# Fri3d_2020_Time_Blaster_01.net
KiCad netlist of a schematic drawn in Altium Designer
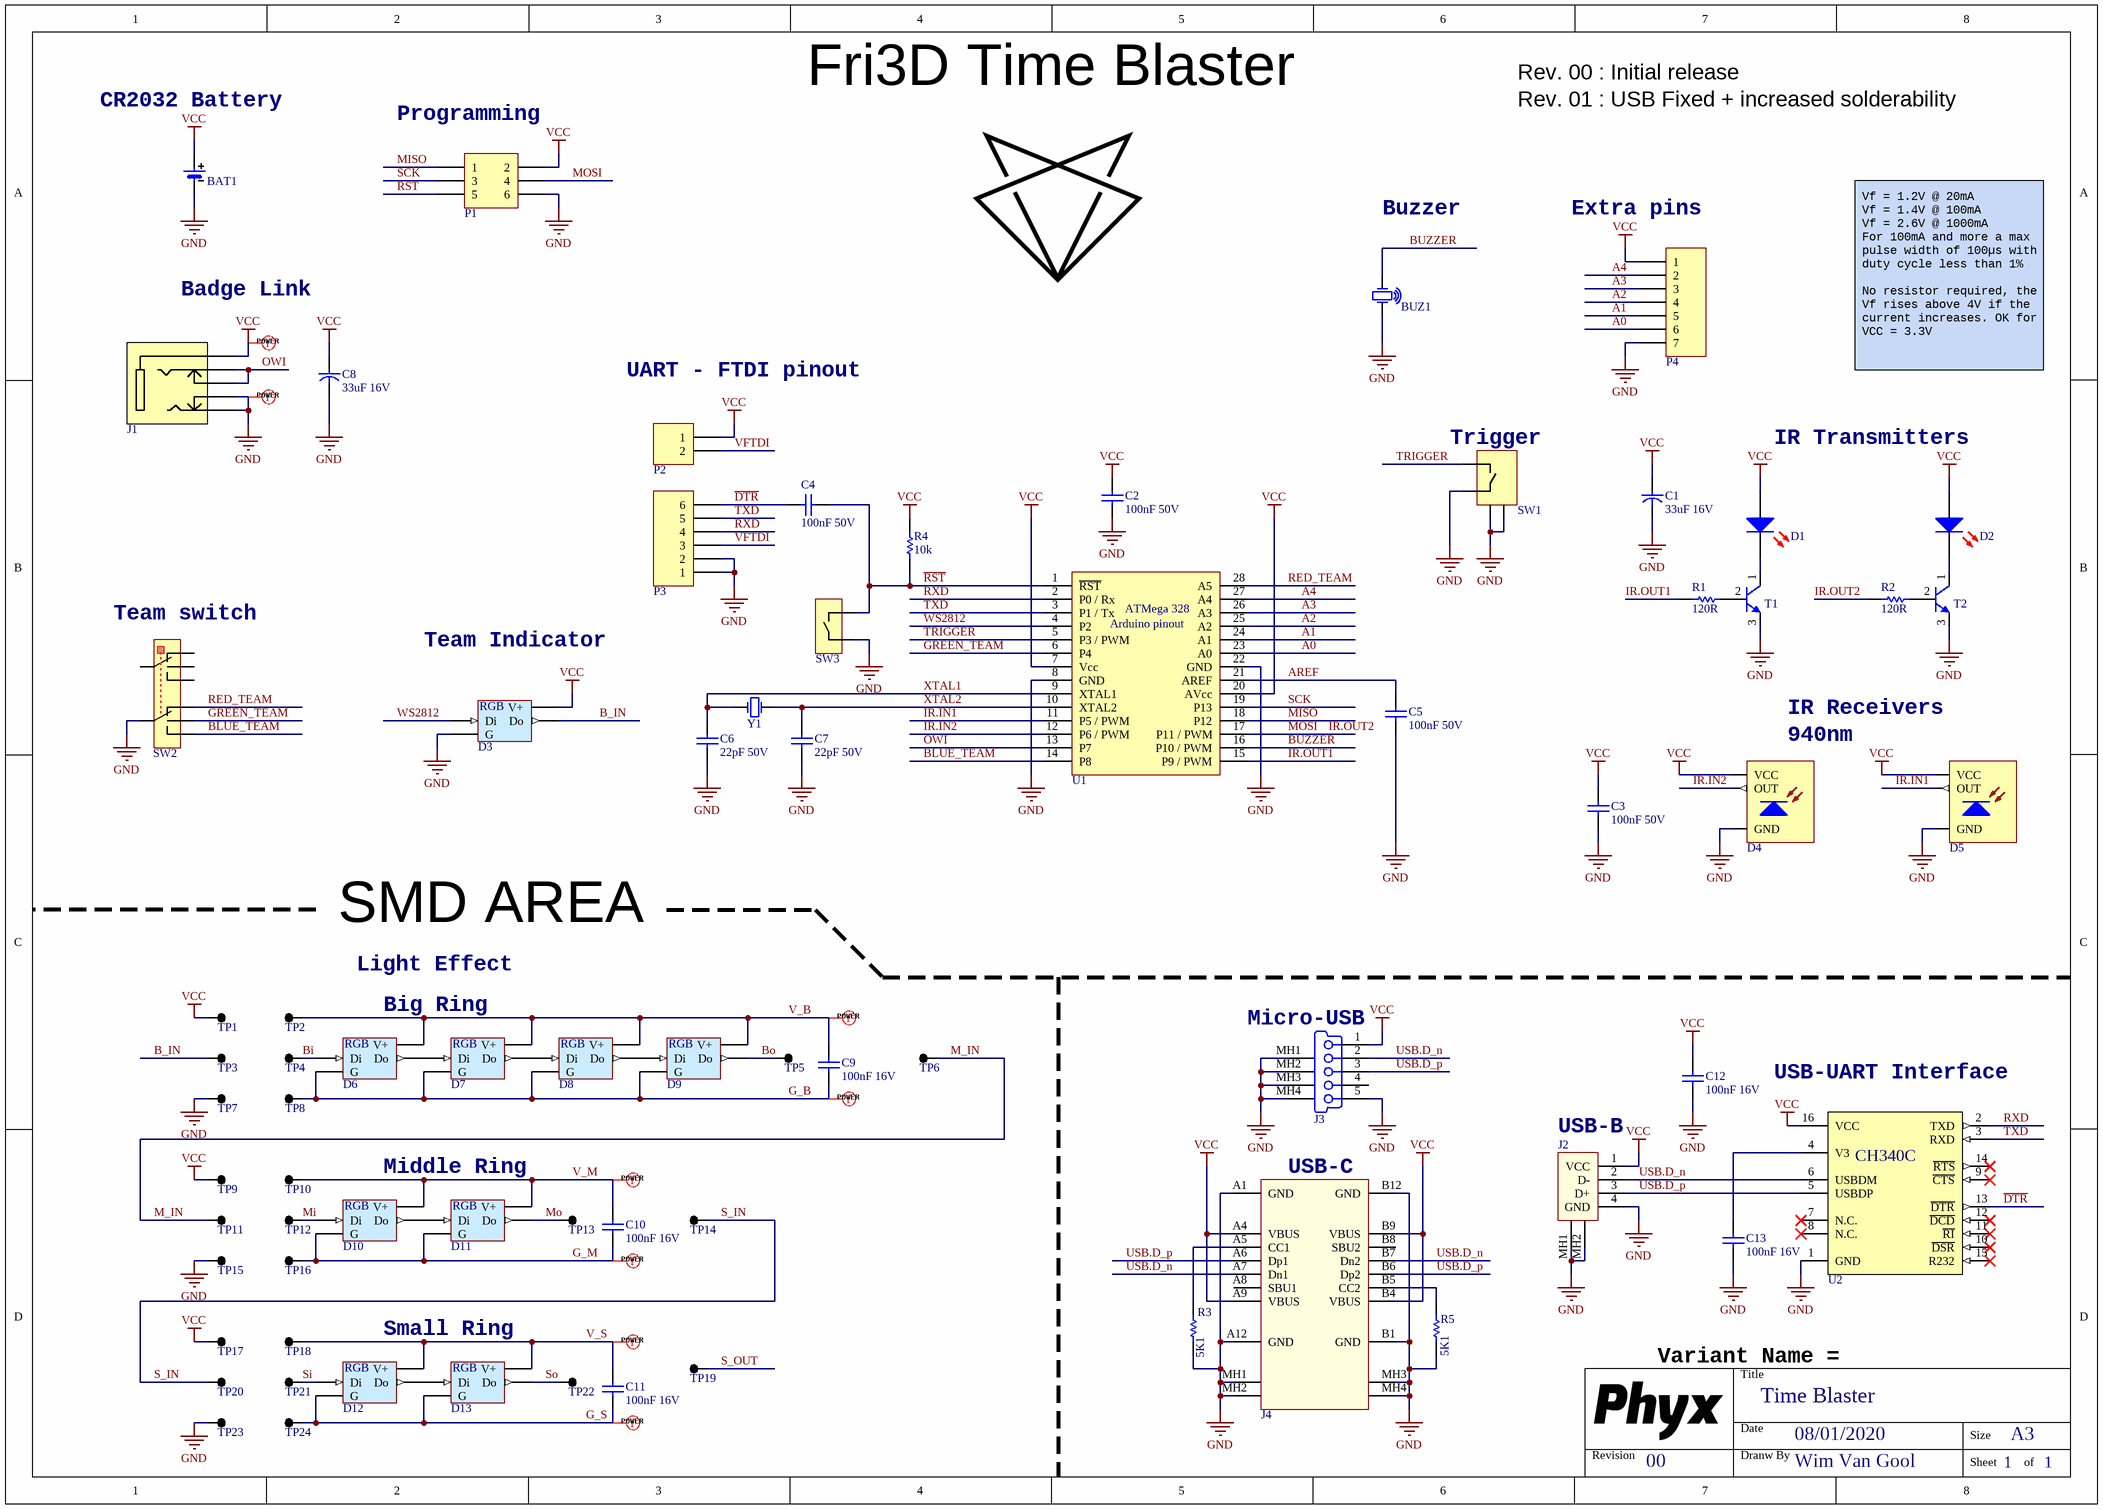
[diagram p0: Fri3d_2020_Time_Blaster_01.SchDoc]

(export (version "E")
  (design (tool "Eeschema 10.0.6"))
  (components
    (comp (ref "BAT1")
      (value "CR2032 Battery Holder")
      (footprint "BAT_CR2032_China")
      (description "=Description")
      (libsource (lib "Phyx_Components") (part "BAT_2"))
    )
    (comp (ref "BUZ1")
      (value "14x14x7mm Piezo Buzzer Transducer 80dB")
      (footprint "CUI_CEP-1162")
      (description "Crystal Oscillator")
      (libsource (lib "Phyx_Components") (part "Buzzer"))
    )
    (comp (ref "C1")
      (value "33uF 16V")
      (footprint "C_4x7_1.5mm")
      (description "Capacitor electrolyt")
      (fields (field (name "Comment") "CAP_POL"))
      (libsource (lib "Phyx_Components") (part "CAP_POL"))
    )
    (comp (ref "C2")
      (value "100nF 50V")
      (footprint "C_5.08mm")
      (description "Capacitor Ceramic")
      (fields (field (name "Comment") "CAP_CERAMIC"))
      (libsource (lib "Phyx_Components") (part "CAP_CERAMIC"))
    )
    (comp (ref "C3")
      (value "100nF 50V")
      (footprint "C_5.08mm")
      (description "Capacitor Ceramic")
      (fields (field (name "Comment") "CAP_CERAMIC"))
      (libsource (lib "Phyx_Components") (part "CAP_CERAMIC"))
    )
    (comp (ref "C4")
      (value "100nF 50V")
      (footprint "C_5.08mm")
      (description "Capacitor Ceramic")
      (fields (field (name "Comment") "CAP_CERAMIC"))
      (libsource (lib "Phyx_Components") (part "CAP_CERAMIC"))
    )
    (comp (ref "C5")
      (value "100nF 50V")
      (footprint "C_5.08mm")
      (description "Capacitor Ceramic")
      (fields (field (name "Comment") "CAP_CERAMIC"))
      (libsource (lib "Phyx_Components") (part "CAP_CERAMIC"))
    )
    (comp (ref "C6")
      (value "22pF 50V")
      (footprint "C_5.08mm")
      (description "Capacitor Ceramic")
      (fields (field (name "Comment") "CAP_CERAMIC"))
      (libsource (lib "Phyx_Components") (part "CAP_CERAMIC"))
    )
    (comp (ref "C7")
      (value "22pF 50V")
      (footprint "C_5.08mm")
      (description "Capacitor Ceramic")
      (fields (field (name "Comment") "CAP_CERAMIC"))
      (libsource (lib "Phyx_Components") (part "CAP_CERAMIC"))
    )
    (comp (ref "C8")
      (value "33uF 16V")
      (footprint "C_4x7_1.5mm")
      (description "Capacitor electrolyt")
      (fields (field (name "Comment") "CAP_POL"))
      (libsource (lib "Phyx_Components") (part "CAP_POL"))
    )
    (comp (ref "C9")
      (value "100nF 16V")
      (footprint "C0805_N")
      (description "Capacitor Ceramic")
      (fields (field (name "Comment") "CAP_CERAMIC"))
      (libsource (lib "Phyx_Components") (part "CAP_CERAMIC"))
    )
    (comp (ref "C10")
      (value "100nF 16V")
      (footprint "C0805_N")
      (description "Capacitor Ceramic")
      (fields (field (name "Comment") "CAP_CERAMIC"))
      (libsource (lib "Phyx_Components") (part "CAP_CERAMIC"))
    )
    (comp (ref "C11")
      (value "100nF 16V")
      (footprint "C0805_N")
      (description "Capacitor Ceramic")
      (fields (field (name "Comment") "CAP_CERAMIC"))
      (libsource (lib "Phyx_Components") (part "CAP_CERAMIC"))
    )
    (comp (ref "C12")
      (value "100nF 16V")
      (footprint "C0805_N")
      (description "Capacitor Ceramic")
      (fields (field (name "Comment") "CAP_CERAMIC"))
      (libsource (lib "Phyx_Components") (part "CAP_CERAMIC"))
    )
    (comp (ref "C13")
      (value "100nF 16V")
      (footprint "C0805_N")
      (description "Capacitor Ceramic")
      (fields (field (name "Comment") "CAP_CERAMIC"))
      (libsource (lib "Phyx_Components") (part "CAP_CERAMIC"))
    )
    (comp (ref "D1")
      (value "5mm IR LED, 940nm, 100mA, 1.35V, 25Deg")
      (footprint "LED_5MM_RD")
      (description "=Description")
      (libsource (lib "Phyx_Components") (part "LED_RED"))
    )
    (comp (ref "D2")
      (value "5mm IR LED, 940nm, 100mA, 1.35V, 25Deg")
      (footprint "LED_5MM_RD")
      (description "=Description")
      (libsource (lib "Phyx_Components") (part "LED_RED"))
    )
    (comp (ref "D3")
      (value "WS2812 based digital RGB LED 5mm")
      (footprint "LED_5mm_RGB")
      (description "=Description")
      (libsource (lib "Phyx_Components") (part "LED_RGB_WS2812B_5mm"))
    )
    (comp (ref "D4")
      (value "IRM-3638N3F14 Infrared Receiver 38 kHz 45° 2.7-5.5V")
      (footprint "VIS_TSOP381x_BENT")
      (description "=Description")
      (libsource (lib "Phyx_Components") (part "PHO_IR_TSOP381x"))
    )
    (comp (ref "D5")
      (value "IRM-3638N3F14 Infrared Receiver 38 kHz 45° 2.7-5.5V")
      (footprint "VIS_TSOP381x_BENT")
      (description "=Description")
      (libsource (lib "Phyx_Components") (part "PHO_IR_TSOP381x"))
    )
    (comp (ref "D6")
      (value "WS2812 based digital RGB LED 5050 Black package")
      (footprint "LED_5050_WS2812B_BLACK")
      (description "=Description")
      (libsource (lib "Phyx_Components") (part "LED_RGB_WS2812B_5050"))
    )
    (comp (ref "D7")
      (value "WS2812 based digital RGB LED 5050 Black package")
      (footprint "LED_5050_WS2812B_BLACK")
      (description "=Description")
      (libsource (lib "Phyx_Components") (part "LED_RGB_WS2812B_5050"))
    )
    (comp (ref "D8")
      (value "WS2812 based digital RGB LED 5050 Black package")
      (footprint "LED_5050_WS2812B_BLACK")
      (description "=Description")
      (libsource (lib "Phyx_Components") (part "LED_RGB_WS2812B_5050"))
    )
    (comp (ref "D9")
      (value "WS2812 based digital RGB LED 5050 Black package")
      (footprint "LED_5050_WS2812B_BLACK")
      (description "=Description")
      (libsource (lib "Phyx_Components") (part "LED_RGB_WS2812B_5050"))
    )
    (comp (ref "D10")
      (value "WS2812 based digital RGB LED 5050 Black package")
      (footprint "LED_5050_WS2812B_BLACK")
      (description "=Description")
      (libsource (lib "Phyx_Components") (part "LED_RGB_WS2812B_5050"))
    )
    (comp (ref "D11")
      (value "WS2812 based digital RGB LED 5050 Black package")
      (footprint "LED_5050_WS2812B_BLACK")
      (description "=Description")
      (libsource (lib "Phyx_Components") (part "LED_RGB_WS2812B_5050"))
    )
    (comp (ref "D12")
      (value "WS2812 based digital RGB LED 5050 Black package")
      (footprint "LED_5050_WS2812B_BLACK")
      (description "=Description")
      (libsource (lib "Phyx_Components") (part "LED_RGB_WS2812B_5050"))
    )
    (comp (ref "D13")
      (value "WS2812 based digital RGB LED 5050 Black package")
      (footprint "LED_5050_WS2812B_BLACK")
      (description "=Description")
      (libsource (lib "Phyx_Components") (part "LED_RGB_WS2812B_5050"))
    )
    (comp (ref "J1")
      (value "3.5mm jack, dual switch, black, 3 contacts")
      (footprint "CUI_SJ1-3525NG")
      (description "=Description")
      (libsource (lib "Phyx_Components") (part "CUI_SJ1-3525NG"))
    )
    (comp (ref "J2")
      (value "Vertical USB B 61400416121")
      (footprint "WE_61400416121")
      (libsource (lib "Phyx_Components") (part "USB_A"))
    )
    (comp (ref "J3")
      (value "XKB U254-051T-4BH81-S2S Micro USB")
      (footprint "XKB_U254-051T-4BH81-S2S")
      (libsource (lib "Phyx_Components") (part "USB_OTG_Mini-B"))
    )
    (comp (ref "J4")
      (value "USB 2.0 C Reversible Receptacle Horizontal")
      (footprint "HRO_TYPE-C-31-M-12")
      (libsource (lib "Phyx_Components") (part "USB_C_16_4"))
    )
    (comp (ref "P1")
      (value "Boxed Header 3X2")
      (footprint "B_HDR2X3")
      (libsource (lib "Phyx_Components") (part "Header 3X2"))
    )
    (comp (ref "P2")
      (value "Easy to solder connection")
      (footprint "SOLDER_SW_V_1MM")
      (libsource (lib "Phyx_Components") (part "Header 2"))
    )
    (comp (ref "P3")
      (value "Header 6")
      (footprint "HDR1X6")
      (libsource (lib "Phyx_Components") (part "Header 6"))
    )
    (comp (ref "P4")
      (value "Header 7")
      (footprint "HDR1X7")
      (libsource (lib "Phyx_Components") (part "Header 7"))
    )
    (comp (ref "R1")
      (value "120R")
      (footprint "RES_10mm")
      (fields (field (name "Comment") "RESISTOR"))
      (libsource (lib "Phyx_Components") (part "RESISTOR"))
    )
    (comp (ref "R2")
      (value "120R")
      (footprint "RES_10mm")
      (fields (field (name "Comment") "RESISTOR"))
      (libsource (lib "Phyx_Components") (part "RESISTOR"))
    )
    (comp (ref "R3")
      (value "5K1")
      (footprint "R0805_N")
      (fields (field (name "Comment") "RESISTOR"))
      (libsource (lib "Phyx_Components") (part "RESISTOR"))
    )
    (comp (ref "R4")
      (value "10k")
      (footprint "RES_10mm")
      (fields (field (name "Comment") "RESISTOR"))
      (libsource (lib "Phyx_Components") (part "RESISTOR"))
    )
    (comp (ref "R5")
      (value "5K1")
      (footprint "R0805_N")
      (fields (field (name "Comment") "RESISTOR"))
      (libsource (lib "Phyx_Components") (part "RESISTOR"))
    )
    (comp (ref "SW1")
      (value "Tact switch, RA, 3,85mm")
      (footprint "TACTSW_RA_385")
      (libsource (lib "Phyx_Components") (part "SW_TACT_RA"))
    )
    (comp (ref "SW2")
      (value "Slide switch dual pole triple throw")
      (footprint "CK_JS203011CQN")
      (libsource (lib "Phyx_Components") (part "SW_2P3T"))
    )
    (comp (ref "SW3")
      (value "Default TH TACT")
      (footprint "TACTSW")
      (libsource (lib "Phyx_Components") (part "SW_TACT"))
    )
    (comp (ref "T1")
      (value "0.2A 40V 100hfe NPN Transistor")
      (footprint "TO-92A _EASY")
      (libsource (lib "Phyx_Components") (part "NPN_EBC"))
    )
    (comp (ref "T2")
      (value "0.2A 40V 100hfe NPN Transistor")
      (footprint "TO-92A _EASY")
      (libsource (lib "Phyx_Components") (part "NPN_EBC"))
    )
    (comp (ref "TP1")
      (value "TEST_PAD")
      (footprint "TP_2x3mm")
      (libsource (lib "Phyx_Components") (part "TEST_PAD"))
    )
    (comp (ref "TP2")
      (value "TEST_PAD")
      (footprint "TP_2x3mm")
      (libsource (lib "Phyx_Components") (part "TEST_PAD"))
    )
    (comp (ref "TP3")
      (value "TEST_PAD")
      (footprint "TP_2x3mm")
      (libsource (lib "Phyx_Components") (part "TEST_PAD"))
    )
    (comp (ref "TP4")
      (value "TEST_PAD")
      (footprint "TP_2x3mm")
      (libsource (lib "Phyx_Components") (part "TEST_PAD"))
    )
    (comp (ref "TP5")
      (value "TEST_PAD")
      (footprint "TP_2x3mm")
      (libsource (lib "Phyx_Components") (part "TEST_PAD"))
    )
    (comp (ref "TP6")
      (value "TEST_PAD")
      (footprint "TP_2x3mm")
      (libsource (lib "Phyx_Components") (part "TEST_PAD"))
    )
    (comp (ref "TP7")
      (value "TEST_PAD")
      (footprint "TP_2x3mm")
      (libsource (lib "Phyx_Components") (part "TEST_PAD"))
    )
    (comp (ref "TP8")
      (value "TEST_PAD")
      (footprint "TP_2x3mm")
      (libsource (lib "Phyx_Components") (part "TEST_PAD"))
    )
    (comp (ref "TP9")
      (value "TEST_PAD")
      (footprint "TP_2x3mm")
      (libsource (lib "Phyx_Components") (part "TEST_PAD"))
    )
    (comp (ref "TP10")
      (value "TEST_PAD")
      (footprint "TP_2x3mm")
      (libsource (lib "Phyx_Components") (part "TEST_PAD"))
    )
    (comp (ref "TP11")
      (value "TEST_PAD")
      (footprint "TP_2x3mm")
      (libsource (lib "Phyx_Components") (part "TEST_PAD"))
    )
    (comp (ref "TP12")
      (value "TEST_PAD")
      (footprint "TP_2x3mm")
      (libsource (lib "Phyx_Components") (part "TEST_PAD"))
    )
    (comp (ref "TP13")
      (value "TEST_PAD")
      (footprint "TP_2x3mm")
      (libsource (lib "Phyx_Components") (part "TEST_PAD"))
    )
    (comp (ref "TP14")
      (value "TEST_PAD")
      (footprint "TP_2x3mm")
      (libsource (lib "Phyx_Components") (part "TEST_PAD"))
    )
    (comp (ref "TP15")
      (value "TEST_PAD")
      (footprint "TP_2x3mm")
      (libsource (lib "Phyx_Components") (part "TEST_PAD"))
    )
    (comp (ref "TP16")
      (value "TEST_PAD")
      (footprint "TP_2x3mm")
      (libsource (lib "Phyx_Components") (part "TEST_PAD"))
    )
    (comp (ref "TP17")
      (value "TEST_PAD")
      (footprint "TP_2x3mm")
      (libsource (lib "Phyx_Components") (part "TEST_PAD"))
    )
    (comp (ref "TP18")
      (value "TEST_PAD")
      (footprint "TP_2x3mm")
      (libsource (lib "Phyx_Components") (part "TEST_PAD"))
    )
    (comp (ref "TP19")
      (value "TEST_PAD")
      (footprint "TP_2x3mm")
      (libsource (lib "Phyx_Components") (part "TEST_PAD"))
    )
    (comp (ref "TP20")
      (value "TEST_PAD")
      (footprint "TP_2x3mm")
      (libsource (lib "Phyx_Components") (part "TEST_PAD"))
    )
    (comp (ref "TP21")
      (value "TEST_PAD")
      (footprint "TP_2x3mm")
      (libsource (lib "Phyx_Components") (part "TEST_PAD"))
    )
    (comp (ref "TP22")
      (value "TEST_PAD")
      (footprint "TP_2x3mm")
      (libsource (lib "Phyx_Components") (part "TEST_PAD"))
    )
    (comp (ref "TP23")
      (value "TEST_PAD")
      (footprint "TP_2x3mm")
      (libsource (lib "Phyx_Components") (part "TEST_PAD"))
    )
    (comp (ref "TP24")
      (value "TEST_PAD")
      (footprint "TP_2x3mm")
      (libsource (lib "Phyx_Components") (part "TEST_PAD"))
    )
    (comp (ref "U1")
      (value "8-bit MCU")
      (footprint "DIP_N_28")
      (libsource (lib "Phyx_Components") (part "ATMega328_DIP28"))
    )
    (comp (ref "U2")
      (value "USB to full UART with internal crystal")
      (footprint "SOIC_N_16")
      (description "=Description")
      (libsource (lib "Phyx_Components") (part "CH340C"))
    )
    (comp (ref "Y1")
      (value "16MHz 18pF HC49US")
      (footprint "HC49US")
      (description "Crystal Oscillator")
      (libsource (lib "Phyx_Components") (part "XTAL"))
    )
  )
  (nets
    (net (code "1") (name "/A0") (class "Default")
      (node (ref "P4") (pin "6") (pinfunction "6_6") (pintype "passive"))
      (node (ref "U1") (pin "23") (pinfunction "A0_23") (pintype "passive"))
    )
    (net (code "2") (name "/A1") (class "Default")
      (node (ref "P4") (pin "5") (pinfunction "5_5") (pintype "passive"))
      (node (ref "U1") (pin "24") (pinfunction "A1_24") (pintype "passive"))
    )
    (net (code "3") (name "/A2") (class "Default")
      (node (ref "P4") (pin "4") (pinfunction "4_4") (pintype "passive"))
      (node (ref "U1") (pin "25") (pinfunction "A2_25") (pintype "passive"))
    )
    (net (code "4") (name "/A3") (class "Default")
      (node (ref "P4") (pin "3") (pinfunction "3_3") (pintype "passive"))
      (node (ref "U1") (pin "26") (pinfunction "A3_26") (pintype "passive"))
    )
    (net (code "5") (name "/A4") (class "Default")
      (node (ref "P4") (pin "2") (pinfunction "2_2") (pintype "passive"))
      (node (ref "U1") (pin "27") (pinfunction "A4_27") (pintype "passive"))
    )
    (net (code "6") (name "/AREF") (class "Default")
      (node (ref "C5") (pin "1") (pinfunction "1_1") (pintype "passive"))
      (node (ref "U1") (pin "21") (pinfunction "AREF_21") (pintype "passive"))
    )
    (net (code "7") (name "/BLUE_TEAM") (class "Default")
      (node (ref "SW2") (pin "8") (pinfunction "8_8") (pintype "passive"))
      (node (ref "U1") (pin "14") (pinfunction "P8_14") (pintype "passive"))
    )
    (net (code "8") (name "/BUZZER") (class "Default")
      (node (ref "BUZ1") (pin "2") (pinfunction "OSC2_2") (pintype "passive"))
      (node (ref "U1") (pin "16") (pinfunction "P10_/_PWM_16") (pintype "passive"))
    )
    (net (code "9") (name "/B_IN") (class "Default")
      (node (ref "D3") (pin "1") (pinfunction "Do_1") (pintype "output"))
      (node (ref "TP3") (pin "1") (pinfunction "1_1") (pintype "passive"))
    )
    (net (code "10") (name "/Bi") (class "Default")
      (node (ref "D6") (pin "4") (pinfunction "Di_4") (pintype "input"))
      (node (ref "TP4") (pin "1") (pinfunction "1_1") (pintype "passive"))
    )
    (net (code "11") (name "/Bo") (class "Default")
      (node (ref "D9") (pin "2") (pinfunction "Do_2") (pintype "output"))
      (node (ref "TP5") (pin "1") (pinfunction "1_1") (pintype "passive"))
    )
    (net (code "12") (name "/GREEN_TEAM") (class "Default")
      (node (ref "SW2") (pin "6") (pinfunction "6_6") (pintype "passive"))
      (node (ref "U1") (pin "6") (pinfunction "P4_6") (pintype "passive"))
    )
    (net (code "13") (name "/G_B") (class "Default")
      (node (ref "C9") (pin "2") (pinfunction "2_2") (pintype "passive"))
      (node (ref "D6") (pin "3") (pinfunction "G_3") (pintype "power_in"))
      (node (ref "D7") (pin "3") (pinfunction "G_3") (pintype "power_in"))
      (node (ref "D8") (pin "3") (pinfunction "G_3") (pintype "power_in"))
      (node (ref "D9") (pin "3") (pinfunction "G_3") (pintype "power_in"))
      (node (ref "TP8") (pin "1") (pinfunction "1_1") (pintype "passive"))
    )
    (net (code "14") (name "/G_M") (class "Default")
      (node (ref "C10") (pin "2") (pinfunction "2_2") (pintype "passive"))
      (node (ref "D10") (pin "3") (pinfunction "G_3") (pintype "power_in"))
      (node (ref "D11") (pin "3") (pinfunction "G_3") (pintype "power_in"))
      (node (ref "TP16") (pin "1") (pinfunction "1_1") (pintype "passive"))
    )
    (net (code "15") (name "/G_S") (class "Default")
      (node (ref "C11") (pin "2") (pinfunction "2_2") (pintype "passive"))
      (node (ref "D12") (pin "3") (pinfunction "G_3") (pintype "power_in"))
      (node (ref "D13") (pin "3") (pinfunction "G_3") (pintype "power_in"))
      (node (ref "TP24") (pin "1") (pinfunction "1_1") (pintype "passive"))
    )
    (net (code "16") (name "/IR.IN1") (class "Default")
      (node (ref "D5") (pin "1") (pinfunction "OUT_1") (pintype "output"))
      (node (ref "U1") (pin "11") (pinfunction "P5_/_PWM_11") (pintype "passive"))
    )
    (net (code "17") (name "/IR.IN2") (class "Default")
      (node (ref "D4") (pin "1") (pinfunction "OUT_1") (pintype "output"))
      (node (ref "U1") (pin "12") (pinfunction "P6_/_PWM_12") (pintype "passive"))
    )
    (net (code "18") (name "/IR.OUT1") (class "Default")
      (node (ref "R1") (pin "2") (pinfunction "2_2") (pintype "passive"))
      (node (ref "U1") (pin "15") (pinfunction "P9_/_PWM_15") (pintype "passive"))
    )
    (net (code "19") (name "/IR.OUT2") (class "Default")
      (node (ref "P1") (pin "4") (pinfunction "4_4") (pintype "passive"))
      (node (ref "R2") (pin "2") (pinfunction "2_2") (pintype "passive"))
      (node (ref "U1") (pin "17") (pinfunction "P11_/_PWM_17") (pintype "passive"))
    )
    (net (code "20") (name "/MISO") (class "Default")
      (node (ref "P1") (pin "1") (pinfunction "1_1") (pintype "passive"))
      (node (ref "U1") (pin "18") (pinfunction "P12_18") (pintype "passive"))
    )
    (net (code "21") (name "/M_IN") (class "Default")
      (node (ref "TP11") (pin "1") (pinfunction "1_1") (pintype "passive"))
      (node (ref "TP6") (pin "1") (pinfunction "1_1") (pintype "passive"))
    )
    (net (code "22") (name "/Mi") (class "Default")
      (node (ref "D10") (pin "4") (pinfunction "Di_4") (pintype "input"))
      (node (ref "TP12") (pin "1") (pinfunction "1_1") (pintype "passive"))
    )
    (net (code "23") (name "/Mo") (class "Default")
      (node (ref "D11") (pin "2") (pinfunction "Do_2") (pintype "output"))
      (node (ref "TP13") (pin "1") (pinfunction "1_1") (pintype "passive"))
    )
    (net (code "24") (name "/OWI") (class "Default")
      (node (ref "J1") (pin "3") (pinfunction "Ring_3") (pintype "passive"))
      (node (ref "J1") (pin "5") (pinfunction "5_5") (pintype "passive"))
      (node (ref "U1") (pin "13") (pinfunction "P7_13") (pintype "passive"))
    )
    (net (code "25") (name "/RED_TEAM") (class "Default")
      (node (ref "SW2") (pin "5") (pinfunction "5_5") (pintype "passive"))
      (node (ref "U1") (pin "28") (pinfunction "A5_28") (pintype "passive"))
    )
    (net (code "26") (name "/RXD") (class "Default")
      (node (ref "P3") (pin "4") (pinfunction "4_4") (pintype "passive"))
      (node (ref "U1") (pin "2") (pinfunction "P0_/_Rx_2") (pintype "passive"))
      (node (ref "U2") (pin "2") (pinfunction "TXD_2") (pintype "output"))
    )
    (net (code "27") (name "/SCK") (class "Default")
      (node (ref "P1") (pin "3") (pinfunction "3_3") (pintype "passive"))
      (node (ref "U1") (pin "19") (pinfunction "P13_19") (pintype "passive"))
    )
    (net (code "28") (name "/S_IN") (class "Default")
      (node (ref "TP14") (pin "1") (pinfunction "1_1") (pintype "passive"))
      (node (ref "TP20") (pin "1") (pinfunction "1_1") (pintype "passive"))
    )
    (net (code "29") (name "/S_OUT") (class "Default")
      (node (ref "TP19") (pin "1") (pinfunction "1_1") (pintype "passive"))
    )
    (net (code "30") (name "/Si") (class "Default")
      (node (ref "D12") (pin "4") (pinfunction "Di_4") (pintype "input"))
      (node (ref "TP21") (pin "1") (pinfunction "1_1") (pintype "passive"))
    )
    (net (code "31") (name "/So") (class "Default")
      (node (ref "D13") (pin "2") (pinfunction "Do_2") (pintype "output"))
      (node (ref "TP22") (pin "1") (pinfunction "1_1") (pintype "passive"))
    )
    (net (code "32") (name "/TRIGGER") (class "Default")
      (node (ref "SW1") (pin "1") (pinfunction "1_1") (pintype "passive"))
      (node (ref "U1") (pin "5") (pinfunction "P3_/_PWM_5") (pintype "passive"))
    )
    (net (code "33") (name "/TXD") (class "Default")
      (node (ref "P3") (pin "5") (pinfunction "5_5") (pintype "passive"))
      (node (ref "U1") (pin "3") (pinfunction "P1_/_Tx_3") (pintype "passive"))
      (node (ref "U2") (pin "3") (pinfunction "RXD_3") (pintype "input"))
    )
    (net (code "34") (name "/USB.D_n") (class "Default")
      (node (ref "J2") (pin "2") (pinfunction "D-_2") (pintype "passive"))
      (node (ref "J3") (pin "2") (pinfunction "D-_2") (pintype "passive"))
      (node (ref "J4") (pin "A7") (pinfunction "Dn1_A7") (pintype "passive"))
      (node (ref "J4") (pin "B7") (pinfunction "Dn2_B7") (pintype "passive"))
      (node (ref "U2") (pin "6") (pinfunction "USBDM_6") (pintype "passive"))
    )
    (net (code "35") (name "/USB.D_p") (class "Default")
      (node (ref "J2") (pin "3") (pinfunction "D+_3") (pintype "passive"))
      (node (ref "J3") (pin "3") (pinfunction "D+_3") (pintype "passive"))
      (node (ref "J4") (pin "A6") (pinfunction "Dp1_A6") (pintype "passive"))
      (node (ref "J4") (pin "B6") (pinfunction "Dp2_B6") (pintype "passive"))
      (node (ref "U2") (pin "5") (pinfunction "USBDP_5") (pintype "passive"))
    )
    (net (code "36") (name "/VFTDI") (class "Default")
      (node (ref "P2") (pin "2") (pinfunction "2_2") (pintype "passive"))
      (node (ref "P3") (pin "3") (pinfunction "3_3") (pintype "passive"))
    )
    (net (code "37") (name "/V_B") (class "Default")
      (node (ref "C9") (pin "1") (pinfunction "1_1") (pintype "passive"))
      (node (ref "D6") (pin "1") (pinfunction "V+_1") (pintype "power_in"))
      (node (ref "D7") (pin "1") (pinfunction "V+_1") (pintype "power_in"))
      (node (ref "D8") (pin "1") (pinfunction "V+_1") (pintype "power_in"))
      (node (ref "D9") (pin "1") (pinfunction "V+_1") (pintype "power_in"))
      (node (ref "TP2") (pin "1") (pinfunction "1_1") (pintype "passive"))
    )
    (net (code "38") (name "/V_M") (class "Default")
      (node (ref "C10") (pin "1") (pinfunction "1_1") (pintype "passive"))
      (node (ref "D10") (pin "1") (pinfunction "V+_1") (pintype "power_in"))
      (node (ref "D11") (pin "1") (pinfunction "V+_1") (pintype "power_in"))
      (node (ref "TP10") (pin "1") (pinfunction "1_1") (pintype "passive"))
    )
    (net (code "39") (name "/V_S") (class "Default")
      (node (ref "C11") (pin "1") (pinfunction "1_1") (pintype "passive"))
      (node (ref "D12") (pin "1") (pinfunction "V+_1") (pintype "power_in"))
      (node (ref "D13") (pin "1") (pinfunction "V+_1") (pintype "power_in"))
      (node (ref "TP18") (pin "1") (pinfunction "1_1") (pintype "passive"))
    )
    (net (code "40") (name "/WS2812") (class "Default")
      (node (ref "D3") (pin "4") (pinfunction "Di_4") (pintype "input"))
      (node (ref "U1") (pin "4") (pinfunction "P2_4") (pintype "passive"))
    )
    (net (code "41") (name "/XTAL1") (class "Default")
      (node (ref "C6") (pin "1") (pinfunction "1_1") (pintype "passive"))
      (node (ref "U1") (pin "9") (pinfunction "XTAL1_9") (pintype "passive"))
      (node (ref "Y1") (pin "1") (pinfunction "OSC1_1") (pintype "passive"))
    )
    (net (code "42") (name "/XTAL2") (class "Default")
      (node (ref "C7") (pin "1") (pinfunction "1_1") (pintype "passive"))
      (node (ref "U1") (pin "10") (pinfunction "XTAL2_10") (pintype "passive"))
      (node (ref "Y1") (pin "2") (pinfunction "OSC2_2") (pintype "passive"))
    )
    (net (code "43") (name "/~{DTR}") (class "Default")
      (node (ref "C4") (pin "2") (pinfunction "2_2") (pintype "passive"))
      (node (ref "P3") (pin "6") (pinfunction "6_6") (pintype "passive"))
      (node (ref "U2") (pin "13") (pinfunction "~{DTR}_13") (pintype "output"))
    )
    (net (code "44") (name "/~{RST}") (class "Default")
      (node (ref "C4") (pin "1") (pinfunction "1_1") (pintype "passive"))
      (node (ref "P1") (pin "5") (pinfunction "5_5") (pintype "passive"))
      (node (ref "R4") (pin "2") (pinfunction "2_2") (pintype "passive"))
      (node (ref "SW3") (pin "1") (pinfunction "1_1") (pintype "passive"))
      (node (ref "U1") (pin "1") (pinfunction "~{RST}_1") (pintype "passive"))
    )
    (net (code "45") (name "GND") (class "Default")
      (node (ref "BAT1") (pin "2") (pinfunction "2_2") (pintype "passive"))
      (node (ref "BUZ1") (pin "1") (pinfunction "OSC1_1") (pintype "passive"))
      (node (ref "C1") (pin "2") (pinfunction "2_2") (pintype "passive"))
      (node (ref "C12") (pin "2") (pinfunction "2_2") (pintype "passive"))
      (node (ref "C13") (pin "2") (pinfunction "2_2") (pintype "passive"))
      (node (ref "C2") (pin "2") (pinfunction "2_2") (pintype "passive"))
      (node (ref "C3") (pin "2") (pinfunction "2_2") (pintype "passive"))
      (node (ref "C5") (pin "2") (pinfunction "2_2") (pintype "passive"))
      (node (ref "C6") (pin "2") (pinfunction "2_2") (pintype "passive"))
      (node (ref "C7") (pin "2") (pinfunction "2_2") (pintype "passive"))
      (node (ref "C8") (pin "2") (pinfunction "2_2") (pintype "passive"))
      (node (ref "D3") (pin "3") (pinfunction "G_3") (pintype "power_in"))
      (node (ref "D4") (pin "2") (pinfunction "GND_2") (pintype "power_in"))
      (node (ref "D5") (pin "2") (pinfunction "GND_2") (pintype "power_in"))
      (node (ref "J1") (pin "2") (pinfunction "Tip_2") (pintype "passive"))
      (node (ref "J1") (pin "4") (pinfunction "4_4") (pintype "passive"))
      (node (ref "J2") (pin "4") (pinfunction "GND_4") (pintype "passive"))
      (node (ref "J2") (pin "MH1") (pinfunction "Tab_MH1") (pintype "passive"))
      (node (ref "J2") (pin "MH2") (pinfunction "Tab_MH2") (pintype "passive"))
      (node (ref "J3") (pin "5") (pinfunction "GND_5") (pintype "passive"))
      (node (ref "J3") (pin "MH1") (pinfunction "Tab_MH1") (pintype "passive"))
      (node (ref "J3") (pin "MH2") (pinfunction "Tab_MH2") (pintype "passive"))
      (node (ref "J3") (pin "MH3") (pinfunction "Tab_MH3") (pintype "passive"))
      (node (ref "J3") (pin "MH4") (pinfunction "Tab_MH4") (pintype "passive"))
      (node (ref "J4") (pin "A1") (pinfunction "GND_A1") (pintype "passive"))
      (node (ref "J4") (pin "A12") (pinfunction "GND_A12") (pintype "passive"))
      (node (ref "J4") (pin "B1") (pinfunction "GND_B1") (pintype "passive"))
      (node (ref "J4") (pin "B12") (pinfunction "GND_B12") (pintype "passive"))
      (node (ref "J4") (pin "MH1") (pinfunction "Tab_MH1") (pintype "passive"))
      (node (ref "J4") (pin "MH2") (pinfunction "Tab_MH2") (pintype "passive"))
      (node (ref "J4") (pin "MH3") (pinfunction "Tab_MH3") (pintype "passive"))
      (node (ref "J4") (pin "MH4") (pinfunction "Tab_MH4") (pintype "passive"))
      (node (ref "P1") (pin "6") (pinfunction "6_6") (pintype "passive"))
      (node (ref "P3") (pin "1") (pinfunction "1_1") (pintype "passive"))
      (node (ref "P3") (pin "2") (pinfunction "2_2") (pintype "passive"))
      (node (ref "P4") (pin "7") (pinfunction "7_7") (pintype "passive"))
      (node (ref "R3") (pin "2") (pinfunction "2_2") (pintype "passive"))
      (node (ref "R5") (pin "2") (pinfunction "2_2") (pintype "passive"))
      (node (ref "SW1") (pin "2") (pinfunction "2_2") (pintype "passive"))
      (node (ref "SW1") (pin "MH1") (pinfunction "MH1_MH1") (pintype "passive"))
      (node (ref "SW1") (pin "MH2") (pinfunction "MH2_MH2") (pintype "passive"))
      (node (ref "SW2") (pin "7") (pinfunction "7_7") (pintype "passive"))
      (node (ref "SW3") (pin "2") (pinfunction "2_2") (pintype "passive"))
      (node (ref "T1") (pin "3") (pinfunction "E_3") (pintype "passive"))
      (node (ref "T2") (pin "3") (pinfunction "E_3") (pintype "passive"))
      (node (ref "TP15") (pin "1") (pinfunction "1_1") (pintype "passive"))
      (node (ref "TP23") (pin "1") (pinfunction "1_1") (pintype "passive"))
      (node (ref "TP7") (pin "1") (pinfunction "1_1") (pintype "passive"))
      (node (ref "U1") (pin "22") (pinfunction "GND_22") (pintype "power_in"))
      (node (ref "U1") (pin "8") (pinfunction "GND_8") (pintype "power_in"))
      (node (ref "U2") (pin "1") (pinfunction "GND_1") (pintype "power_in"))
    )
    (net (code "46") (name "Net-(D1-K)") (class "Default")
      (node (ref "D1") (pin "2") (pinfunction "K_2") (pintype "passive"))
      (node (ref "T1") (pin "1") (pinfunction "C_1") (pintype "passive"))
    )
    (net (code "47") (name "Net-(D2-K)") (class "Default")
      (node (ref "D2") (pin "2") (pinfunction "K_2") (pintype "passive"))
      (node (ref "T2") (pin "1") (pinfunction "C_1") (pintype "passive"))
    )
    (net (code "48") (name "Net-(D6-Do)") (class "Default")
      (node (ref "D6") (pin "2") (pinfunction "Do_2") (pintype "output"))
      (node (ref "D7") (pin "4") (pinfunction "Di_4") (pintype "input"))
    )
    (net (code "49") (name "Net-(D7-Do)") (class "Default")
      (node (ref "D7") (pin "2") (pinfunction "Do_2") (pintype "output"))
      (node (ref "D8") (pin "4") (pinfunction "Di_4") (pintype "input"))
    )
    (net (code "50") (name "Net-(D8-Do)") (class "Default")
      (node (ref "D8") (pin "2") (pinfunction "Do_2") (pintype "output"))
      (node (ref "D9") (pin "4") (pinfunction "Di_4") (pintype "input"))
    )
    (net (code "51") (name "Net-(D10-Do)") (class "Default")
      (node (ref "D10") (pin "2") (pinfunction "Do_2") (pintype "output"))
      (node (ref "D11") (pin "4") (pinfunction "Di_4") (pintype "input"))
    )
    (net (code "52") (name "Net-(D12-Do)") (class "Default")
      (node (ref "D12") (pin "2") (pinfunction "Do_2") (pintype "output"))
      (node (ref "D13") (pin "4") (pinfunction "Di_4") (pintype "input"))
    )
    (net (code "53") (name "Net-(J4-CC1)") (class "Default")
      (node (ref "J4") (pin "A5") (pinfunction "CC1_A5") (pintype "passive"))
      (node (ref "R3") (pin "1") (pinfunction "1_1") (pintype "passive"))
    )
    (net (code "54") (name "Net-(J4-CC2)") (class "Default")
      (node (ref "J4") (pin "B5") (pinfunction "CC2_B5") (pintype "passive"))
      (node (ref "R5") (pin "1") (pinfunction "1_1") (pintype "passive"))
    )
    (net (code "55") (name "Net-(T1-B)") (class "Default")
      (node (ref "R1") (pin "1") (pinfunction "1_1") (pintype "passive"))
      (node (ref "T1") (pin "2") (pinfunction "B_2") (pintype "passive"))
    )
    (net (code "56") (name "Net-(T2-B)") (class "Default")
      (node (ref "R2") (pin "1") (pinfunction "1_1") (pintype "passive"))
      (node (ref "T2") (pin "2") (pinfunction "B_2") (pintype "passive"))
    )
    (net (code "57") (name "Net-(U2-V3)") (class "Default")
      (node (ref "C13") (pin "1") (pinfunction "1_1") (pintype "passive"))
      (node (ref "U2") (pin "4") (pinfunction "V3_4") (pintype "power_in"))
    )
    (net (code "58") (name "VCC") (class "Default")
      (node (ref "BAT1") (pin "1") (pinfunction "1_1") (pintype "passive"))
      (node (ref "C1") (pin "1") (pinfunction "1_1") (pintype "passive"))
      (node (ref "C12") (pin "1") (pinfunction "1_1") (pintype "passive"))
      (node (ref "C2") (pin "1") (pinfunction "1_1") (pintype "passive"))
      (node (ref "C3") (pin "1") (pinfunction "1_1") (pintype "passive"))
      (node (ref "C8") (pin "1") (pinfunction "1_1") (pintype "passive"))
      (node (ref "D1") (pin "1") (pinfunction "A_1") (pintype "passive"))
      (node (ref "D2") (pin "1") (pinfunction "A_1") (pintype "passive"))
      (node (ref "D3") (pin "2") (pinfunction "V+_2") (pintype "power_in"))
      (node (ref "D4") (pin "3") (pinfunction "VCC_3") (pintype "power_in"))
      (node (ref "D5") (pin "3") (pinfunction "VCC_3") (pintype "power_in"))
      (node (ref "J1") (pin "1") (pinfunction "Sleeve_1") (pintype "passive"))
      (node (ref "J2") (pin "1") (pinfunction "VCC_1") (pintype "passive"))
      (node (ref "J3") (pin "1") (pinfunction "V_BUS_(5V)_1") (pintype "passive"))
      (node (ref "J4") (pin "A4") (pinfunction "VBUS_A4") (pintype "passive"))
      (node (ref "J4") (pin "A9") (pinfunction "VBUS_A9") (pintype "passive"))
      (node (ref "J4") (pin "B4") (pinfunction "VBUS_B4") (pintype "passive"))
      (node (ref "J4") (pin "B9") (pinfunction "VBUS_B9") (pintype "passive"))
      (node (ref "P1") (pin "2") (pinfunction "2_2") (pintype "passive"))
      (node (ref "P2") (pin "1") (pinfunction "1_1") (pintype "passive"))
      (node (ref "P4") (pin "1") (pinfunction "1_1") (pintype "passive"))
      (node (ref "R4") (pin "1") (pinfunction "1_1") (pintype "passive"))
      (node (ref "TP1") (pin "1") (pinfunction "1_1") (pintype "passive"))
      (node (ref "TP17") (pin "1") (pinfunction "1_1") (pintype "passive"))
      (node (ref "TP9") (pin "1") (pinfunction "1_1") (pintype "passive"))
      (node (ref "U1") (pin "20") (pinfunction "AVcc_20") (pintype "power_in"))
      (node (ref "U1") (pin "7") (pinfunction "Vcc_7") (pintype "power_in"))
      (node (ref "U2") (pin "16") (pinfunction "VCC_16") (pintype "power_in"))
    )
    (net (code "59") (name "unconnected-(J3-NC-Pad4)") (class "Default")
      (node (ref "J3") (pin "4") (pinfunction "NC_4") (pintype "passive"))
    )
    (net (code "60") (name "unconnected-(J4-SBU1-PadA8)") (class "Default")
      (node (ref "J4") (pin "A8") (pinfunction "SBU1_A8") (pintype "passive"))
    )
    (net (code "61") (name "unconnected-(J4-SBU2-PadB8)") (class "Default")
      (node (ref "J4") (pin "B8") (pinfunction "SBU2_B8") (pintype "passive"))
    )
    (net (code "62") (name "unconnected-(SW2-Pad1)") (class "Default")
      (node (ref "SW2") (pin "1") (pinfunction "1_1") (pintype "passive"))
    )
    (net (code "63") (name "unconnected-(SW2-Pad2)") (class "Default")
      (node (ref "SW2") (pin "2") (pinfunction "2_2") (pintype "passive"))
    )
    (net (code "64") (name "unconnected-(SW2-Pad3)") (class "Default")
      (node (ref "SW2") (pin "3") (pinfunction "3_3") (pintype "passive"))
    )
    (net (code "65") (name "unconnected-(SW2-Pad4)") (class "Default")
      (node (ref "SW2") (pin "4") (pinfunction "4_4") (pintype "passive"))
    )
    (net (code "66") (name "unconnected-(U2-N.C.-Pad7)") (class "Default")
      (node (ref "U2") (pin "7") (pinfunction "N.C._7") (pintype "passive+no_connect"))
    )
    (net (code "67") (name "unconnected-(U2-N.C.-Pad8)") (class "Default")
      (node (ref "U2") (pin "8") (pinfunction "N.C._8") (pintype "passive+no_connect"))
    )
    (net (code "68") (name "unconnected-(U2-R232-Pad15)") (class "Default")
      (node (ref "U2") (pin "15") (pinfunction "R232_15") (pintype "input+no_connect"))
    )
    (net (code "69") (name "unconnected-(U2-~{CTS}-Pad9)") (class "Default")
      (node (ref "U2") (pin "9") (pinfunction "~{CTS}_9") (pintype "input+no_connect"))
    )
    (net (code "70") (name "unconnected-(U2-~{DCD}-Pad12)") (class "Default")
      (node (ref "U2") (pin "12") (pinfunction "~{DCD}_12") (pintype "input+no_connect"))
    )
    (net (code "71") (name "unconnected-(U2-~{DSR}-Pad10)") (class "Default")
      (node (ref "U2") (pin "10") (pinfunction "~{DSR}_10") (pintype "input+no_connect"))
    )
    (net (code "72") (name "unconnected-(U2-~{RI}-Pad11)") (class "Default")
      (node (ref "U2") (pin "11") (pinfunction "~{RI}_11") (pintype "input+no_connect"))
    )
    (net (code "73") (name "unconnected-(U2-~{RTS}-Pad14)") (class "Default")
      (node (ref "U2") (pin "14") (pinfunction "~{RTS}_14") (pintype "output+no_connect"))
    )
  )
)
